# lfsensor.net
KiCad netlist of a schematic drawn in EAGLE
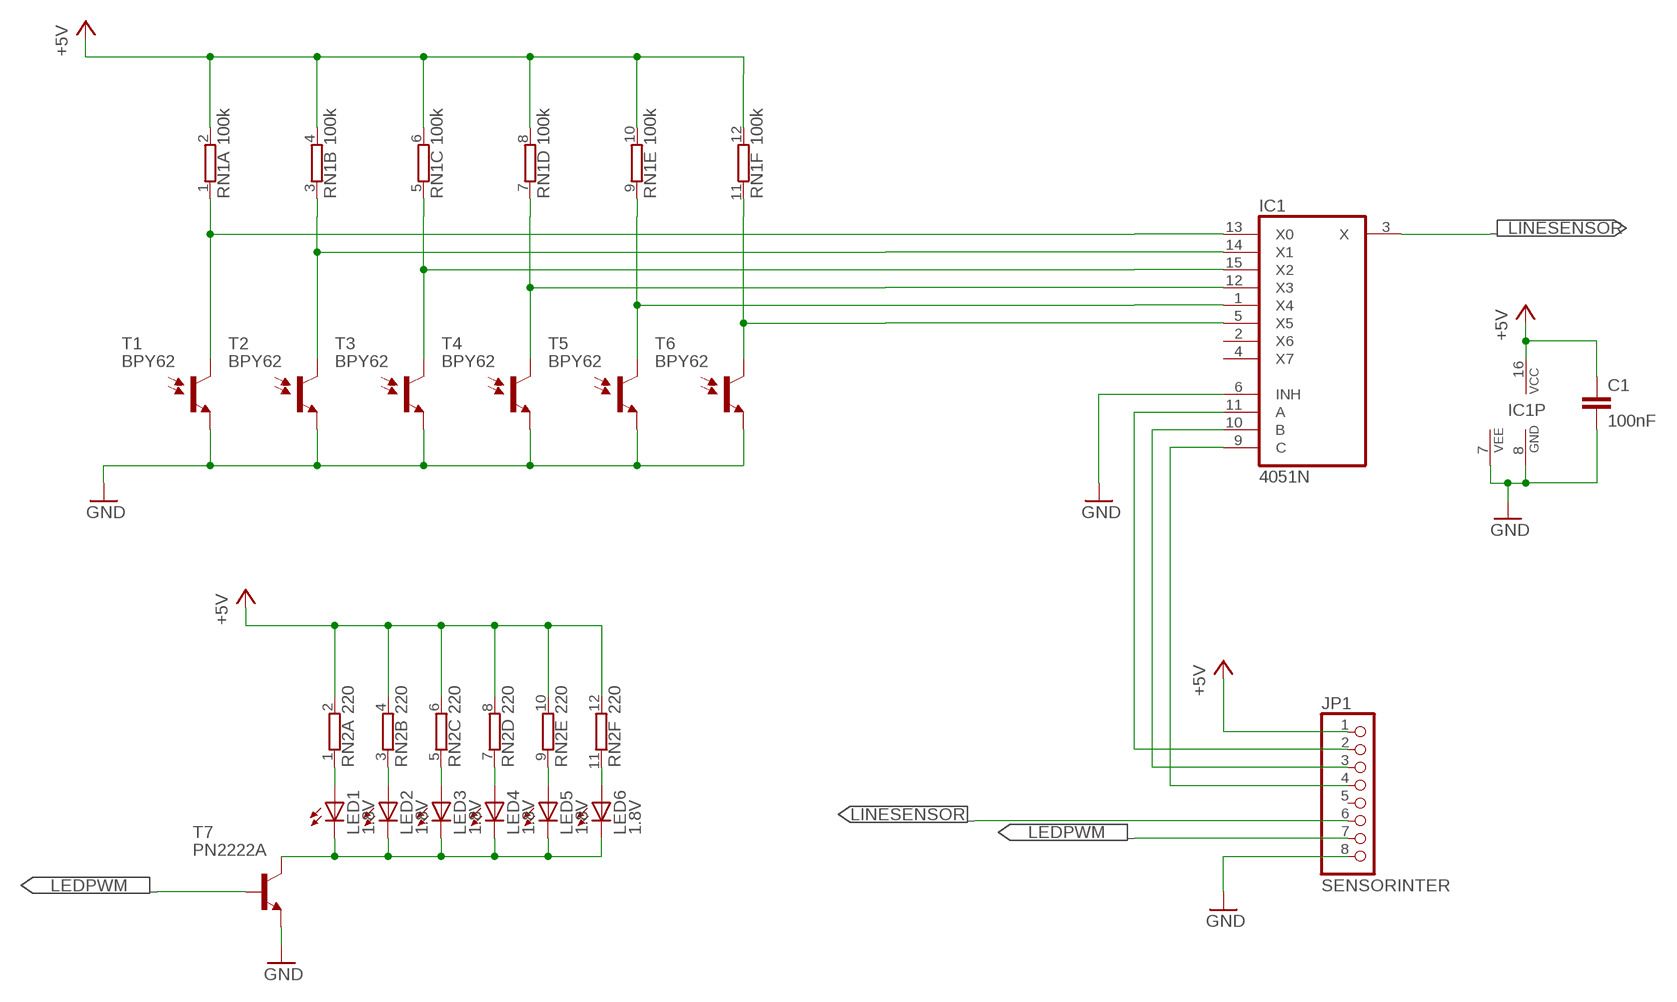
[diagram p0: schematic, sheet 1]

(export (version "E")
  (design (tool "Eeschema 10.0.6"))
  (components
    (comp (ref "C1")
      (value "100nF")
      (footprint "eagle-import:C050-024X044")
      (libsource (lib "eagle-import") (part "C-EU050-024X044"))
    )
    (comp (ref "IC1")
      (value "4051N")
      (footprint "eagle-import:DIL16")
      (libsource (lib "eagle-import") (part "4051N"))
    )
    (comp (ref "JP1")
      (value "SENSORINTER")
      (footprint "eagle-import:1X08")
      (libsource (lib "eagle-import") (part "PINHD-1X8"))
    )
    (comp (ref "LED1")
      (value "1.8V")
      (footprint "eagle-import:LED5MM")
      (libsource (lib "eagle-import") (part "LED5MM"))
    )
    (comp (ref "LED2")
      (value "1.8V")
      (footprint "eagle-import:LED5MM")
      (libsource (lib "eagle-import") (part "LED5MM"))
    )
    (comp (ref "LED3")
      (value "1.8V")
      (footprint "eagle-import:LED5MM")
      (libsource (lib "eagle-import") (part "LED5MM"))
    )
    (comp (ref "LED4")
      (value "1.8V")
      (footprint "eagle-import:LED5MM")
      (libsource (lib "eagle-import") (part "LED5MM"))
    )
    (comp (ref "LED5")
      (value "1.8V")
      (footprint "eagle-import:LED5MM")
      (libsource (lib "eagle-import") (part "LED5MM"))
    )
    (comp (ref "LED6")
      (value "1.8V")
      (footprint "eagle-import:LED5MM")
      (libsource (lib "eagle-import") (part "LED5MM"))
    )
    (comp (ref "RN1")
      (value "100k")
      (footprint "eagle-import:SIL12")
      (libsource (lib "eagle-import") (part "E6R"))
    )
    (comp (ref "RN2")
      (value "220")
      (footprint "eagle-import:SIL12")
      (libsource (lib "eagle-import") (part "E6R"))
    )
    (comp (ref "T1")
      (value "BPY62")
      (footprint "eagle-import:TO18")
      (libsource (lib "eagle-import") (part "BPY62"))
    )
    (comp (ref "T2")
      (value "BPY62")
      (footprint "eagle-import:TO18")
      (libsource (lib "eagle-import") (part "BPY62"))
    )
    (comp (ref "T3")
      (value "BPY62")
      (footprint "eagle-import:TO18")
      (libsource (lib "eagle-import") (part "BPY62"))
    )
    (comp (ref "T4")
      (value "BPY62")
      (footprint "eagle-import:TO18")
      (libsource (lib "eagle-import") (part "BPY62"))
    )
    (comp (ref "T5")
      (value "BPY62")
      (footprint "eagle-import:TO18")
      (libsource (lib "eagle-import") (part "BPY62"))
    )
    (comp (ref "T6")
      (value "BPY62")
      (footprint "eagle-import:TO18")
      (libsource (lib "eagle-import") (part "BPY62"))
    )
    (comp (ref "T7")
      (value "PN2222A")
      (footprint "eagle-import:TO92")
      (libsource (lib "eagle-import") (part "PN2222A"))
    )
  )
  (nets
    (net (code "1") (name "+5V") (class "Default")
      (node (ref "C1") (pin "1") (pinfunction "1_1") (pintype "passive"))
      (node (ref "IC1") (pin "16") (pinfunction "VCC_16") (pintype "power_in"))
      (node (ref "JP1") (pin "1") (pinfunction "1_1") (pintype "passive"))
      (node (ref "RN1") (pin "10") (pinfunction "2_10") (pintype "passive"))
      (node (ref "RN1") (pin "12") (pinfunction "2_12") (pintype "passive"))
      (node (ref "RN1") (pin "2") (pinfunction "2_2") (pintype "passive"))
      (node (ref "RN1") (pin "4") (pinfunction "2_4") (pintype "passive"))
      (node (ref "RN1") (pin "6") (pinfunction "2_6") (pintype "passive"))
      (node (ref "RN1") (pin "8") (pinfunction "2_8") (pintype "passive"))
      (node (ref "RN2") (pin "10") (pinfunction "2_10") (pintype "passive"))
      (node (ref "RN2") (pin "12") (pinfunction "2_12") (pintype "passive"))
      (node (ref "RN2") (pin "2") (pinfunction "2_2") (pintype "passive"))
      (node (ref "RN2") (pin "4") (pinfunction "2_4") (pintype "passive"))
      (node (ref "RN2") (pin "6") (pinfunction "2_6") (pintype "passive"))
      (node (ref "RN2") (pin "8") (pinfunction "2_8") (pintype "passive"))
    )
    (net (code "2") (name "/LEDPWM") (class "Default")
      (node (ref "JP1") (pin "7") (pinfunction "7_7") (pintype "passive"))
      (node (ref "T7") (pin "2") (pinfunction "B_2") (pintype "passive"))
    )
    (net (code "3") (name "/LINESENSOR") (class "Default")
      (node (ref "IC1") (pin "3") (pinfunction "X_3") (pintype "bidirectional"))
      (node (ref "JP1") (pin "6") (pinfunction "6_6") (pintype "passive"))
    )
    (net (code "4") (name "GND") (class "Default")
      (node (ref "C1") (pin "2") (pinfunction "2_2") (pintype "passive"))
      (node (ref "IC1") (pin "6") (pinfunction "INH_6") (pintype "input"))
      (node (ref "IC1") (pin "7") (pinfunction "VEE_7") (pintype "power_in"))
      (node (ref "IC1") (pin "8") (pinfunction "GND_8") (pintype "power_in"))
      (node (ref "JP1") (pin "8") (pinfunction "8_8") (pintype "passive"))
      (node (ref "T1") (pin "1") (pinfunction "E_1") (pintype "passive"))
      (node (ref "T2") (pin "1") (pinfunction "E_1") (pintype "passive"))
      (node (ref "T3") (pin "1") (pinfunction "E_1") (pintype "passive"))
      (node (ref "T4") (pin "1") (pinfunction "E_1") (pintype "passive"))
      (node (ref "T5") (pin "1") (pinfunction "E_1") (pintype "passive"))
      (node (ref "T6") (pin "1") (pinfunction "E_1") (pintype "passive"))
      (node (ref "T7") (pin "3") (pinfunction "E_3") (pintype "passive"))
    )
    (net (code "5") (name "Net-(IC1A-A)") (class "Default")
      (node (ref "IC1") (pin "11") (pinfunction "A_11") (pintype "input"))
      (node (ref "JP1") (pin "2") (pinfunction "2_2") (pintype "passive"))
    )
    (net (code "6") (name "Net-(IC1A-B)") (class "Default")
      (node (ref "IC1") (pin "10") (pinfunction "B_10") (pintype "input"))
      (node (ref "JP1") (pin "3") (pinfunction "3_3") (pintype "passive"))
    )
    (net (code "7") (name "Net-(IC1A-C)") (class "Default")
      (node (ref "IC1") (pin "9") (pinfunction "C_9") (pintype "input"))
      (node (ref "JP1") (pin "4") (pinfunction "4_4") (pintype "passive"))
    )
    (net (code "8") (name "Net-(IC1A-X0)") (class "Default")
      (node (ref "IC1") (pin "13") (pinfunction "X0_13") (pintype "bidirectional"))
      (node (ref "RN1") (pin "1") (pinfunction "1_1") (pintype "passive"))
      (node (ref "T1") (pin "2") (pinfunction "C_2") (pintype "passive"))
    )
    (net (code "9") (name "Net-(IC1A-X1)") (class "Default")
      (node (ref "IC1") (pin "14") (pinfunction "X1_14") (pintype "bidirectional"))
      (node (ref "RN1") (pin "3") (pinfunction "1_3") (pintype "passive"))
      (node (ref "T2") (pin "2") (pinfunction "C_2") (pintype "passive"))
    )
    (net (code "10") (name "Net-(IC1A-X2)") (class "Default")
      (node (ref "IC1") (pin "15") (pinfunction "X2_15") (pintype "bidirectional"))
      (node (ref "RN1") (pin "5") (pinfunction "1_5") (pintype "passive"))
      (node (ref "T3") (pin "2") (pinfunction "C_2") (pintype "passive"))
    )
    (net (code "11") (name "Net-(IC1A-X3)") (class "Default")
      (node (ref "IC1") (pin "12") (pinfunction "X3_12") (pintype "bidirectional"))
      (node (ref "RN1") (pin "7") (pinfunction "1_7") (pintype "passive"))
      (node (ref "T4") (pin "2") (pinfunction "C_2") (pintype "passive"))
    )
    (net (code "12") (name "Net-(IC1A-X4)") (class "Default")
      (node (ref "IC1") (pin "1") (pinfunction "X4_1") (pintype "bidirectional"))
      (node (ref "RN1") (pin "9") (pinfunction "1_9") (pintype "passive"))
      (node (ref "T5") (pin "2") (pinfunction "C_2") (pintype "passive"))
    )
    (net (code "13") (name "Net-(IC1A-X5)") (class "Default")
      (node (ref "IC1") (pin "5") (pinfunction "X5_5") (pintype "bidirectional"))
      (node (ref "RN1") (pin "11") (pinfunction "1_11") (pintype "passive"))
      (node (ref "T6") (pin "2") (pinfunction "C_2") (pintype "passive"))
    )
    (net (code "14") (name "Net-(LED1-C)") (class "Default")
      (node (ref "LED1") (pin "K") (pinfunction "C_K") (pintype "passive"))
      (node (ref "LED2") (pin "K") (pinfunction "C_K") (pintype "passive"))
      (node (ref "LED3") (pin "K") (pinfunction "C_K") (pintype "passive"))
      (node (ref "LED4") (pin "K") (pinfunction "C_K") (pintype "passive"))
      (node (ref "LED5") (pin "K") (pinfunction "C_K") (pintype "passive"))
      (node (ref "LED6") (pin "K") (pinfunction "C_K") (pintype "passive"))
      (node (ref "T7") (pin "1") (pinfunction "C_1") (pintype "passive"))
    )
    (net (code "15") (name "Net-(LED1-PadA)") (class "Default")
      (node (ref "LED1") (pin "A") (pinfunction "A_A") (pintype "passive"))
      (node (ref "RN2") (pin "1") (pinfunction "1_1") (pintype "passive"))
    )
    (net (code "16") (name "Net-(RN2B-1)") (class "Default")
      (node (ref "LED2") (pin "A") (pinfunction "A_A") (pintype "passive"))
      (node (ref "RN2") (pin "3") (pinfunction "1_3") (pintype "passive"))
    )
    (net (code "17") (name "Net-(RN2C-1)") (class "Default")
      (node (ref "LED3") (pin "A") (pinfunction "A_A") (pintype "passive"))
      (node (ref "RN2") (pin "5") (pinfunction "1_5") (pintype "passive"))
    )
    (net (code "18") (name "Net-(RN2D-1)") (class "Default")
      (node (ref "LED4") (pin "A") (pinfunction "A_A") (pintype "passive"))
      (node (ref "RN2") (pin "7") (pinfunction "1_7") (pintype "passive"))
    )
    (net (code "19") (name "Net-(RN2E-1)") (class "Default")
      (node (ref "LED5") (pin "A") (pinfunction "A_A") (pintype "passive"))
      (node (ref "RN2") (pin "9") (pinfunction "1_9") (pintype "passive"))
    )
    (net (code "20") (name "Net-(RN2F-1)") (class "Default")
      (node (ref "LED6") (pin "A") (pinfunction "A_A") (pintype "passive"))
      (node (ref "RN2") (pin "11") (pinfunction "1_11") (pintype "passive"))
    )
    (net (code "21") (name "unconnected-(IC1A-X6-Pad2)") (class "Default")
      (node (ref "IC1") (pin "2") (pinfunction "X6_2") (pintype "bidirectional"))
    )
    (net (code "22") (name "unconnected-(IC1A-X7-Pad4)") (class "Default")
      (node (ref "IC1") (pin "4") (pinfunction "X7_4") (pintype "bidirectional"))
    )
    (net (code "23") (name "unconnected-(JP1-Pad5)") (class "Default")
      (node (ref "JP1") (pin "5") (pinfunction "5_5") (pintype "passive"))
    )
  )
)
